# Adafruit_Servo_HAT_rev_A.net
KiCad netlist of a schematic drawn in EAGLE
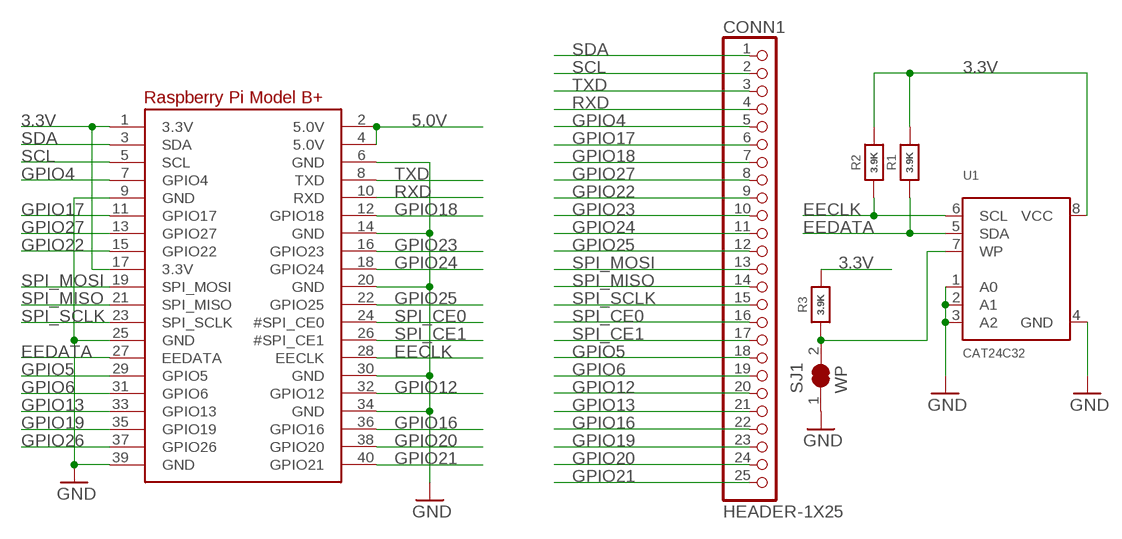
[diagram p0: schematic, sheet 1]
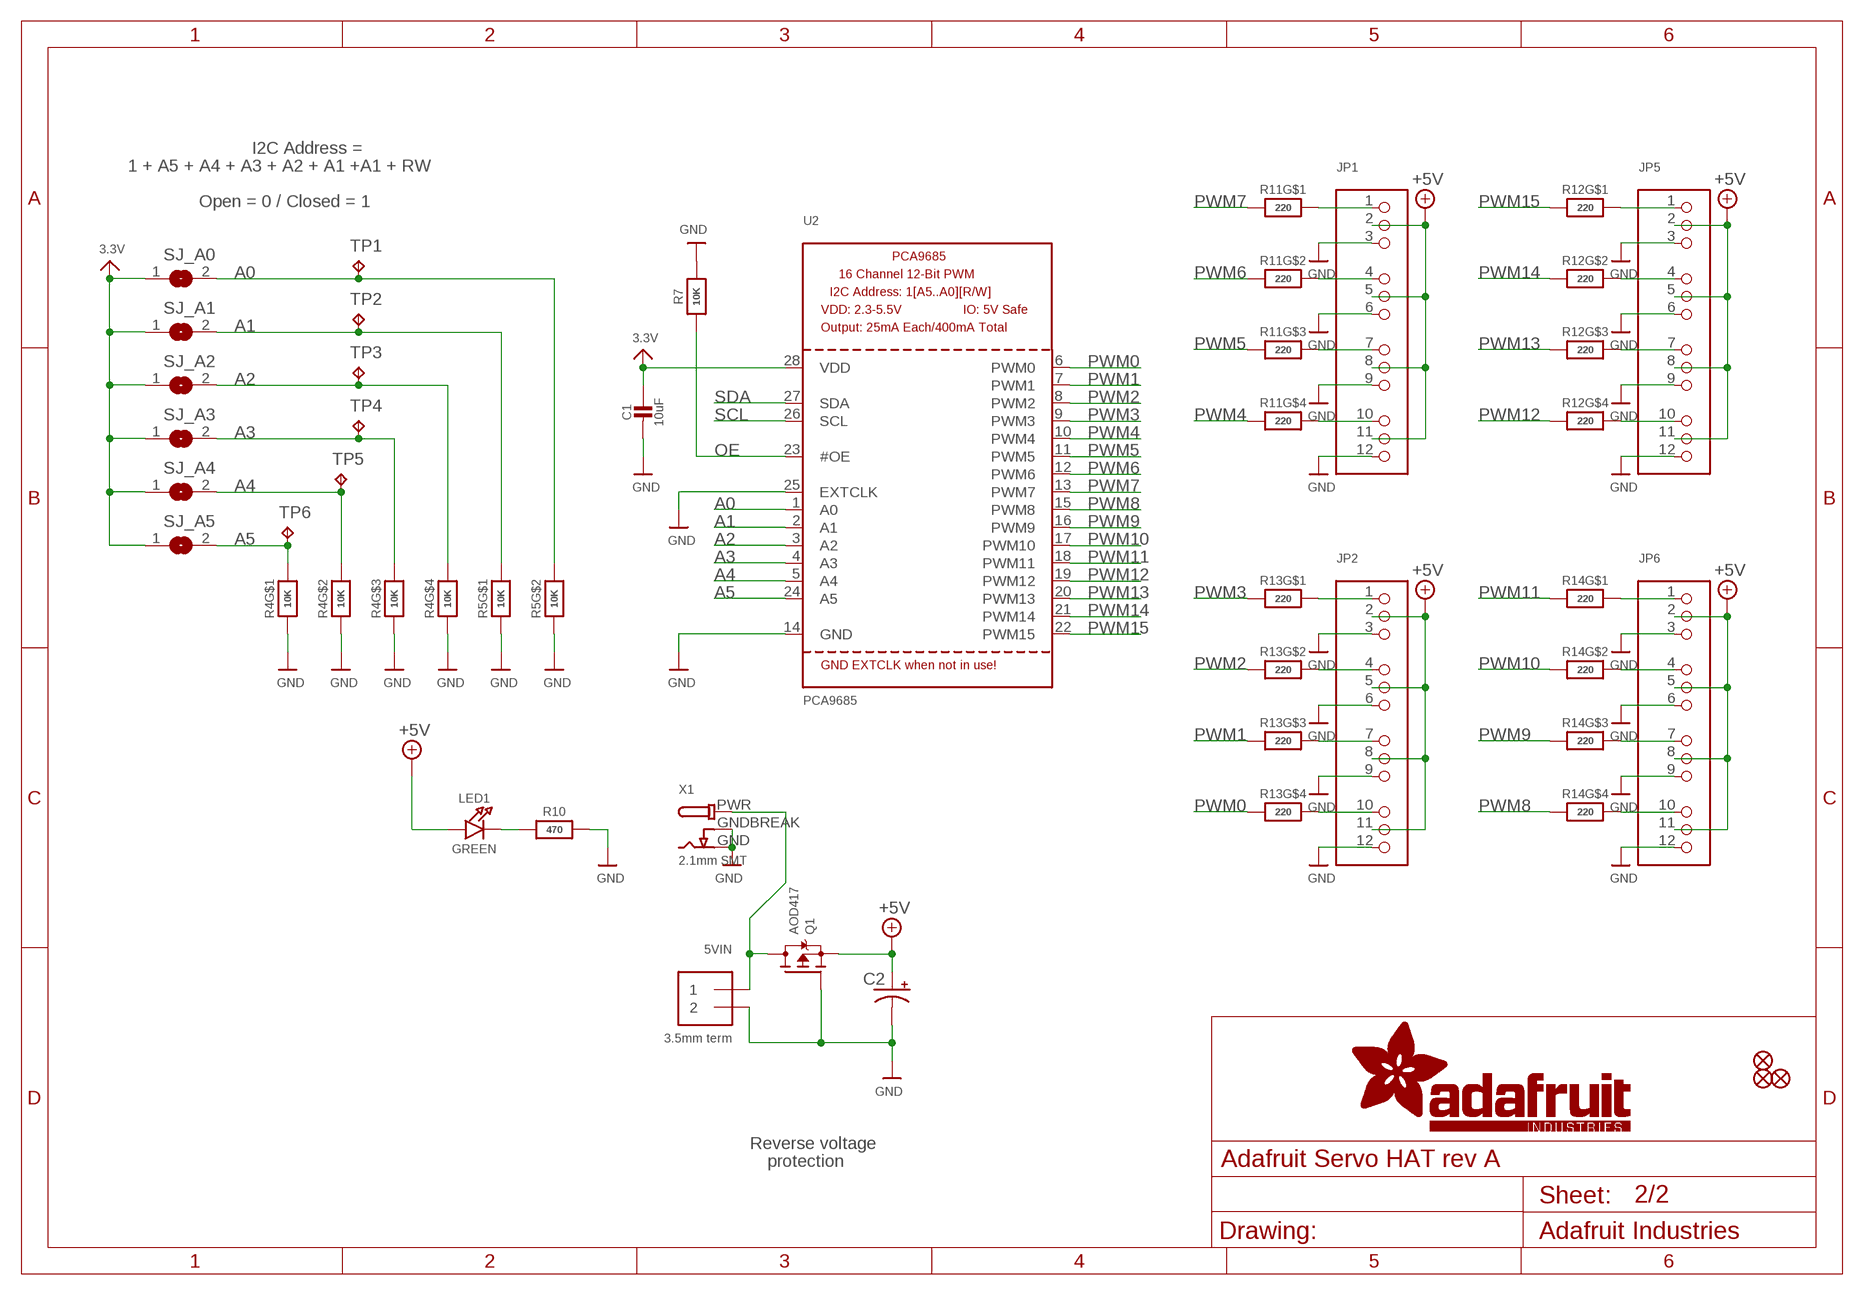
[diagram p1: schematic, sheet 2]

(export (version "E")
  (design (tool "Eeschema 10.0.6"))
  (components
    (comp (ref "5VIN")
      (value "3.5mm term")
      (footprint "eagle-import:TERMBLOCK_1X2-3.5MM")
      (libsource (lib "eagle-import") (part "TERMBLOCK_1X2"))
    )
    (comp (ref "C1")
      (value "10uF")
      (footprint "eagle-import:0805-NO")
      (libsource (lib "eagle-import") (part "CAP_CERAMIC0805-NOOUTLINE"))
    )
    (comp (ref "C2")
      (value "CPOL-USE3.5-8")
      (footprint "eagle-import:E3,5-8")
      (libsource (lib "eagle-import") (part "CPOL-USE3.5-8"))
    )
    (comp (ref "FID1")
      (value "FIDUCIAL\"\"")
      (footprint "eagle-import:FIDUCIAL_1MM")
      (libsource (lib "eagle-import") (part "FIDUCIAL{dblquote}{dblquote}"))
    )
    (comp (ref "FID2")
      (value "FIDUCIAL\"\"")
      (footprint "eagle-import:FIDUCIAL_1MM")
      (libsource (lib "eagle-import") (part "FIDUCIAL{dblquote}{dblquote}"))
    )
    (comp (ref "FID3")
      (value "FIDUCIAL\"\"")
      (footprint "eagle-import:FIDUCIAL_1MM")
      (fields (field (name "BOM") "EXCLUDE"))
      (libsource (lib "eagle-import") (part "FIDUCIAL{dblquote}{dblquote}"))
    )
    (comp (ref "JP1")
      (value "HEADER-3X04")
      (footprint "eagle-import:3X04")
      (libsource (lib "eagle-import") (part "HEADER-3X04"))
    )
    (comp (ref "JP2")
      (value "HEADER-3X04")
      (footprint "eagle-import:3X04")
      (libsource (lib "eagle-import") (part "HEADER-3X04"))
    )
    (comp (ref "JP5")
      (value "HEADER-3X04")
      (footprint "eagle-import:3X04")
      (libsource (lib "eagle-import") (part "HEADER-3X04"))
    )
    (comp (ref "JP6")
      (value "HEADER-3X04")
      (footprint "eagle-import:3X04")
      (libsource (lib "eagle-import") (part "HEADER-3X04"))
    )
    (comp (ref "LED1")
      (value "GREEN")
      (footprint "eagle-import:CHIPLED_0805_NOOUTLINE")
      (libsource (lib "eagle-import") (part "LED0805_NOOUTLINE"))
    )
    (comp (ref "Q1")
      (value "AOD417")
      (footprint "eagle-import:TO252")
      (libsource (lib "eagle-import") (part "MOSFET-PTO252"))
    )
    (comp (ref "R4")
      (value "10K")
      (footprint "eagle-import:RESPACK_4X0603")
      (libsource (lib "eagle-import") (part "RESISTOR_4PACK"))
    )
    (comp (ref "R5")
      (value "10K")
      (footprint "eagle-import:RESPACK_4X0603")
      (libsource (lib "eagle-import") (part "RESISTOR_4PACK"))
    )
    (comp (ref "R7")
      (value "10K")
      (footprint "eagle-import:0805-NO")
      (libsource (lib "eagle-import") (part "RESISTOR0805_NOOUTLINE"))
    )
    (comp (ref "R10")
      (value "470")
      (footprint "eagle-import:_0805MP")
      (libsource (lib "eagle-import") (part "RESISTOR_0805MP"))
    )
    (comp (ref "R11")
      (value "220")
      (footprint "eagle-import:RESPACK_4X0603")
      (libsource (lib "eagle-import") (part "RESISTOR_4PACK"))
    )
    (comp (ref "R12")
      (value "220")
      (footprint "eagle-import:RESPACK_4X0603")
      (libsource (lib "eagle-import") (part "RESISTOR_4PACK"))
    )
    (comp (ref "R13")
      (value "220")
      (footprint "eagle-import:RESPACK_4X0603")
      (libsource (lib "eagle-import") (part "RESISTOR_4PACK"))
    )
    (comp (ref "R14")
      (value "220")
      (footprint "eagle-import:RESPACK_4X0603")
      (libsource (lib "eagle-import") (part "RESISTOR_4PACK"))
    )
    (comp (ref "SJ_A0")
      (value "SOLDERJUMPERREFLOW_NOPASTE")
      (footprint "eagle-import:SOLDERJUMPER_REFLOW_NOPASTE")
      (libsource (lib "eagle-import") (part "SOLDERJUMPERREFLOW_NOPASTE"))
    )
    (comp (ref "SJ_A1")
      (value "SOLDERJUMPERREFLOW_NOPASTE")
      (footprint "eagle-import:SOLDERJUMPER_REFLOW_NOPASTE")
      (libsource (lib "eagle-import") (part "SOLDERJUMPERREFLOW_NOPASTE"))
    )
    (comp (ref "SJ_A2")
      (value "SOLDERJUMPERREFLOW_NOPASTE")
      (footprint "eagle-import:SOLDERJUMPER_REFLOW_NOPASTE")
      (libsource (lib "eagle-import") (part "SOLDERJUMPERREFLOW_NOPASTE"))
    )
    (comp (ref "SJ_A3")
      (value "SOLDERJUMPERREFLOW_NOPASTE")
      (footprint "eagle-import:SOLDERJUMPER_REFLOW_NOPASTE")
      (libsource (lib "eagle-import") (part "SOLDERJUMPERREFLOW_NOPASTE"))
    )
    (comp (ref "SJ_A4")
      (value "SOLDERJUMPERREFLOW_NOPASTE")
      (footprint "eagle-import:SOLDERJUMPER_REFLOW_NOPASTE")
      (libsource (lib "eagle-import") (part "SOLDERJUMPERREFLOW_NOPASTE"))
    )
    (comp (ref "SJ_A5")
      (value "SOLDERJUMPERREFLOW_NOPASTE")
      (footprint "eagle-import:SOLDERJUMPER_REFLOW_NOPASTE")
      (libsource (lib "eagle-import") (part "SOLDERJUMPERREFLOW_NOPASTE"))
    )
    (comp (ref "TP1")
      (value "TPB1,27")
      (footprint "eagle-import:B1,27")
      (libsource (lib "eagle-import") (part "TPB1,27"))
    )
    (comp (ref "TP2")
      (value "TPB1,27")
      (footprint "eagle-import:B1,27")
      (libsource (lib "eagle-import") (part "TPB1,27"))
    )
    (comp (ref "TP3")
      (value "TPB1,27")
      (footprint "eagle-import:B1,27")
      (libsource (lib "eagle-import") (part "TPB1,27"))
    )
    (comp (ref "TP4")
      (value "TPB1,27")
      (footprint "eagle-import:B1,27")
      (libsource (lib "eagle-import") (part "TPB1,27"))
    )
    (comp (ref "TP5")
      (value "TPB1,27")
      (footprint "eagle-import:B1,27")
      (libsource (lib "eagle-import") (part "TPB1,27"))
    )
    (comp (ref "TP6")
      (value "TPB1,27")
      (footprint "eagle-import:B1,27")
      (libsource (lib "eagle-import") (part "TPB1,27"))
    )
    (comp (ref "U2")
      (value "PCA9685")
      (footprint "eagle-import:TSSOP28")
      (libsource (lib "eagle-import") (part "PCA9685"))
    )
    (comp (ref "X1")
      (value "2.1mm SMT")
      (footprint "eagle-import:DCJACK_2MM_SMT")
      (libsource (lib "eagle-import") (part "DCBARRELSMT_CORRECT"))
    )
    (comp (ref "CONN1")
      (value "HEADER-1X25")
      (footprint "eagle-import:1X25_ROUND_70MIL")
      (libsource (lib "eagle-import") (part "HEADER-1X25"))
    )
    (comp (ref "R1")
      (value "3.9K")
      (footprint "eagle-import:0805-NO")
      (libsource (lib "eagle-import") (part "RESISTOR0805_NOOUTLINE"))
    )
    (comp (ref "R2")
      (value "3.9K")
      (footprint "eagle-import:0805-NO")
      (libsource (lib "eagle-import") (part "RESISTOR0805_NOOUTLINE"))
    )
    (comp (ref "R3")
      (value "3.9K")
      (footprint "eagle-import:0805-NO")
      (libsource (lib "eagle-import") (part "RESISTOR0805_NOOUTLINE"))
    )
    (comp (ref "RPI1")
      (value "RASPBERRYPI_BPLUS_HATSLOTS")
      (footprint "eagle-import:PI_HAT_SLOTS")
      (libsource (lib "eagle-import") (part "RASPBERRYPI_BPLUS_HATSLOTS"))
    )
    (comp (ref "SJ1")
      (value "WP")
      (footprint "eagle-import:SOLDERJUMPER_CLOSEDWIRE")
      (libsource (lib "eagle-import") (part "SOLDERJUMPER_CLOSED"))
    )
    (comp (ref "U1")
      (value "CAT24C32")
      (footprint "eagle-import:SOIC8_150MIL")
      (libsource (lib "eagle-import") (part "EEPROM_I2C_SOIC8_GENERIC"))
    )
  )
  (nets
    (net (code "1") (name "+5V") (class "Default")
      (node (ref "C2") (pin "+") (pinfunction "+_+") (pintype "passive"))
      (node (ref "JP1") (pin "11") (pinfunction "11_11") (pintype "passive"))
      (node (ref "JP1") (pin "2") (pinfunction "2_2") (pintype "passive"))
      (node (ref "JP1") (pin "5") (pinfunction "5_5") (pintype "passive"))
      (node (ref "JP1") (pin "8") (pinfunction "8_8") (pintype "passive"))
      (node (ref "JP2") (pin "11") (pinfunction "11_11") (pintype "passive"))
      (node (ref "JP2") (pin "2") (pinfunction "2_2") (pintype "passive"))
      (node (ref "JP2") (pin "5") (pinfunction "5_5") (pintype "passive"))
      (node (ref "JP2") (pin "8") (pinfunction "8_8") (pintype "passive"))
      (node (ref "JP5") (pin "11") (pinfunction "11_11") (pintype "passive"))
      (node (ref "JP5") (pin "2") (pinfunction "2_2") (pintype "passive"))
      (node (ref "JP5") (pin "5") (pinfunction "5_5") (pintype "passive"))
      (node (ref "JP5") (pin "8") (pinfunction "8_8") (pintype "passive"))
      (node (ref "JP6") (pin "11") (pinfunction "11_11") (pintype "passive"))
      (node (ref "JP6") (pin "2") (pinfunction "2_2") (pintype "passive"))
      (node (ref "JP6") (pin "5") (pinfunction "5_5") (pintype "passive"))
      (node (ref "JP6") (pin "8") (pinfunction "8_8") (pintype "passive"))
      (node (ref "LED1") (pin "A") (pinfunction "A_A") (pintype "passive"))
      (node (ref "Q1") (pin "2") (pinfunction "S_2") (pintype "passive"))
    )
    (net (code "2") (name "3.3V") (class "Default")
      (node (ref "C1") (pin "1") (pinfunction "1_1") (pintype "passive"))
      (node (ref "R1") (pin "2") (pinfunction "2_2") (pintype "passive"))
      (node (ref "R2") (pin "2") (pinfunction "2_2") (pintype "passive"))
      (node (ref "R3") (pin "2") (pinfunction "2_2") (pintype "passive"))
      (node (ref "RPI1") (pin "1") (pinfunction "3.3V_1") (pintype "power_in"))
      (node (ref "RPI1") (pin "17") (pinfunction "3.3V_17") (pintype "power_in"))
      (node (ref "SJ_A0") (pin "1") (pinfunction "1_1") (pintype "passive"))
      (node (ref "SJ_A1") (pin "1") (pinfunction "1_1") (pintype "passive"))
      (node (ref "SJ_A2") (pin "1") (pinfunction "1_1") (pintype "passive"))
      (node (ref "SJ_A3") (pin "1") (pinfunction "1_1") (pintype "passive"))
      (node (ref "SJ_A4") (pin "1") (pinfunction "1_1") (pintype "passive"))
      (node (ref "SJ_A5") (pin "1") (pinfunction "1_1") (pintype "passive"))
      (node (ref "U1") (pin "8") (pinfunction "VCC_8") (pintype "power_in"))
      (node (ref "U2") (pin "28") (pinfunction "VDD_28") (pintype "power_in"))
    )
    (net (code "3") (name "5.0V") (class "Default")
      (node (ref "RPI1") (pin "2") (pinfunction "5.0V_2") (pintype "power_in"))
      (node (ref "RPI1") (pin "4") (pinfunction "5.0V_4") (pintype "power_in"))
    )
    (net (code "4") (name "A0") (class "Default")
      (node (ref "R5") (pin "7") (pinfunction "2_7") (pintype "passive"))
      (node (ref "SJ_A0") (pin "2") (pinfunction "2_2") (pintype "passive"))
      (node (ref "TP1") (pin "TP") (pinfunction "TP_TP") (pintype "input"))
      (node (ref "U2") (pin "1") (pinfunction "A0_1") (pintype "bidirectional"))
    )
    (net (code "5") (name "A1") (class "Default")
      (node (ref "R5") (pin "8") (pinfunction "2_8") (pintype "passive"))
      (node (ref "SJ_A1") (pin "2") (pinfunction "2_2") (pintype "passive"))
      (node (ref "TP2") (pin "TP") (pinfunction "TP_TP") (pintype "input"))
      (node (ref "U2") (pin "2") (pinfunction "A1_2") (pintype "bidirectional"))
    )
    (net (code "6") (name "A2") (class "Default")
      (node (ref "R4") (pin "5") (pinfunction "2_5") (pintype "passive"))
      (node (ref "SJ_A2") (pin "2") (pinfunction "2_2") (pintype "passive"))
      (node (ref "TP3") (pin "TP") (pinfunction "TP_TP") (pintype "input"))
      (node (ref "U2") (pin "3") (pinfunction "A2_3") (pintype "bidirectional"))
    )
    (net (code "7") (name "A3") (class "Default")
      (node (ref "R4") (pin "6") (pinfunction "2_6") (pintype "passive"))
      (node (ref "SJ_A3") (pin "2") (pinfunction "2_2") (pintype "passive"))
      (node (ref "TP4") (pin "TP") (pinfunction "TP_TP") (pintype "input"))
      (node (ref "U2") (pin "4") (pinfunction "A3_4") (pintype "bidirectional"))
    )
    (net (code "8") (name "A4") (class "Default")
      (node (ref "R4") (pin "7") (pinfunction "2_7") (pintype "passive"))
      (node (ref "SJ_A4") (pin "2") (pinfunction "2_2") (pintype "passive"))
      (node (ref "TP5") (pin "TP") (pinfunction "TP_TP") (pintype "input"))
      (node (ref "U2") (pin "5") (pinfunction "A4_5") (pintype "bidirectional"))
    )
    (net (code "9") (name "A5") (class "Default")
      (node (ref "R4") (pin "8") (pinfunction "2_8") (pintype "passive"))
      (node (ref "SJ_A5") (pin "2") (pinfunction "2_2") (pintype "passive"))
      (node (ref "TP6") (pin "TP") (pinfunction "TP_TP") (pintype "input"))
      (node (ref "U2") (pin "24") (pinfunction "A5_24") (pintype "bidirectional"))
    )
    (net (code "10") (name "EECLK") (class "Default")
      (node (ref "R2") (pin "1") (pinfunction "1_1") (pintype "passive"))
      (node (ref "RPI1") (pin "28") (pinfunction "EECLK_28") (pintype "power_in"))
      (node (ref "U1") (pin "6") (pinfunction "SCL_6") (pintype "input"))
    )
    (net (code "11") (name "EEDATA") (class "Default")
      (node (ref "R1") (pin "1") (pinfunction "1_1") (pintype "passive"))
      (node (ref "RPI1") (pin "27") (pinfunction "EEDATA_27") (pintype "bidirectional"))
      (node (ref "U1") (pin "5") (pinfunction "SDA_5") (pintype "bidirectional"))
    )
    (net (code "12") (name "GND") (class "Default")
      (node (ref "5VIN") (pin "2") (pinfunction "2_2") (pintype "passive"))
      (node (ref "C1") (pin "2") (pinfunction "2_2") (pintype "passive"))
      (node (ref "C2") (pin "-") (pinfunction "-_-") (pintype "passive"))
      (node (ref "JP1") (pin "12") (pinfunction "12_12") (pintype "passive"))
      (node (ref "JP1") (pin "3") (pinfunction "3_3") (pintype "passive"))
      (node (ref "JP1") (pin "6") (pinfunction "6_6") (pintype "passive"))
      (node (ref "JP1") (pin "9") (pinfunction "9_9") (pintype "passive"))
      (node (ref "JP2") (pin "12") (pinfunction "12_12") (pintype "passive"))
      (node (ref "JP2") (pin "3") (pinfunction "3_3") (pintype "passive"))
      (node (ref "JP2") (pin "6") (pinfunction "6_6") (pintype "passive"))
      (node (ref "JP2") (pin "9") (pinfunction "9_9") (pintype "passive"))
      (node (ref "JP5") (pin "12") (pinfunction "12_12") (pintype "passive"))
      (node (ref "JP5") (pin "3") (pinfunction "3_3") (pintype "passive"))
      (node (ref "JP5") (pin "6") (pinfunction "6_6") (pintype "passive"))
      (node (ref "JP5") (pin "9") (pinfunction "9_9") (pintype "passive"))
      (node (ref "JP6") (pin "12") (pinfunction "12_12") (pintype "passive"))
      (node (ref "JP6") (pin "3") (pinfunction "3_3") (pintype "passive"))
      (node (ref "JP6") (pin "6") (pinfunction "6_6") (pintype "passive"))
      (node (ref "JP6") (pin "9") (pinfunction "9_9") (pintype "passive"))
      (node (ref "Q1") (pin "1") (pinfunction "G_1") (pintype "passive"))
      (node (ref "R10") (pin "2") (pinfunction "2_2") (pintype "passive"))
      (node (ref "R4") (pin "1") (pinfunction "1_1") (pintype "passive"))
      (node (ref "R4") (pin "2") (pinfunction "1_2") (pintype "passive"))
      (node (ref "R4") (pin "3") (pinfunction "1_3") (pintype "passive"))
      (node (ref "R4") (pin "4") (pinfunction "1_4") (pintype "passive"))
      (node (ref "R5") (pin "1") (pinfunction "1_1") (pintype "passive"))
      (node (ref "R5") (pin "2") (pinfunction "1_2") (pintype "passive"))
      (node (ref "R7") (pin "2") (pinfunction "2_2") (pintype "passive"))
      (node (ref "RPI1") (pin "14") (pinfunction "GND_14") (pintype "power_in"))
      (node (ref "RPI1") (pin "20") (pinfunction "GND_20") (pintype "power_in"))
      (node (ref "RPI1") (pin "25") (pinfunction "GND_25") (pintype "power_in"))
      (node (ref "RPI1") (pin "30") (pinfunction "GND_30") (pintype "bidirectional"))
      (node (ref "RPI1") (pin "34") (pinfunction "GND_34") (pintype "bidirectional"))
      (node (ref "RPI1") (pin "39") (pinfunction "GND_39") (pintype "power_in"))
      (node (ref "RPI1") (pin "6") (pinfunction "GND_6") (pintype "power_in"))
      (node (ref "RPI1") (pin "9") (pinfunction "GND_9") (pintype "power_in"))
      (node (ref "SJ1") (pin "1") (pinfunction "1_1") (pintype "passive"))
      (node (ref "U1") (pin "1") (pinfunction "A0_1") (pintype "input"))
      (node (ref "U1") (pin "2") (pinfunction "A1_2") (pintype "input"))
      (node (ref "U1") (pin "3") (pinfunction "A2_3") (pintype "input"))
      (node (ref "U1") (pin "4") (pinfunction "GND_4") (pintype "power_in"))
      (node (ref "U2") (pin "14") (pinfunction "GND_14") (pintype "power_in"))
      (node (ref "U2") (pin "25") (pinfunction "EXTCLK_25") (pintype "input"))
      (node (ref "X1") (pin "GND") (pinfunction "GND_GND") (pintype "power_in"))
      (node (ref "X1") (pin "GNDBREAK") (pinfunction "GNDBREAK_GNDBREAK") (pintype "power_in"))
    )
    (net (code "13") (name "GPIO4") (class "Default")
      (node (ref "CONN1") (pin "5") (pinfunction "5_5") (pintype "passive"))
      (node (ref "RPI1") (pin "7") (pinfunction "GPIO4_7") (pintype "bidirectional"))
    )
    (net (code "14") (name "GPIO5") (class "Default")
      (node (ref "CONN1") (pin "18") (pinfunction "18_18") (pintype "passive"))
      (node (ref "RPI1") (pin "29") (pinfunction "GPIO5_29") (pintype "bidirectional"))
    )
    (net (code "15") (name "GPIO6") (class "Default")
      (node (ref "CONN1") (pin "19") (pinfunction "19_19") (pintype "passive"))
      (node (ref "RPI1") (pin "31") (pinfunction "GPIO6_31") (pintype "power_in"))
    )
    (net (code "16") (name "GPIO12") (class "Default")
      (node (ref "CONN1") (pin "20") (pinfunction "20_20") (pintype "passive"))
      (node (ref "RPI1") (pin "32") (pinfunction "GPIO12_32") (pintype "bidirectional"))
    )
    (net (code "17") (name "GPIO13") (class "Default")
      (node (ref "CONN1") (pin "21") (pinfunction "21_21") (pintype "passive"))
      (node (ref "RPI1") (pin "33") (pinfunction "GPIO13_33") (pintype "bidirectional"))
    )
    (net (code "18") (name "GPIO16") (class "Default")
      (node (ref "CONN1") (pin "22") (pinfunction "22_22") (pintype "passive"))
      (node (ref "RPI1") (pin "36") (pinfunction "GPIO16_36") (pintype "power_in"))
    )
    (net (code "19") (name "GPIO17") (class "Default")
      (node (ref "CONN1") (pin "6") (pinfunction "6_6") (pintype "passive"))
      (node (ref "RPI1") (pin "11") (pinfunction "GPIO17_11") (pintype "bidirectional"))
    )
    (net (code "20") (name "GPIO18") (class "Default")
      (node (ref "CONN1") (pin "7") (pinfunction "7_7") (pintype "passive"))
      (node (ref "RPI1") (pin "12") (pinfunction "GPIO18_12") (pintype "bidirectional"))
    )
    (net (code "21") (name "GPIO19") (class "Default")
      (node (ref "CONN1") (pin "23") (pinfunction "23_23") (pintype "passive"))
      (node (ref "RPI1") (pin "35") (pinfunction "GPIO19_35") (pintype "bidirectional"))
    )
    (net (code "22") (name "GPIO20") (class "Default")
      (node (ref "CONN1") (pin "24") (pinfunction "24_24") (pintype "passive"))
      (node (ref "RPI1") (pin "38") (pinfunction "GPIO20_38") (pintype "bidirectional"))
    )
    (net (code "23") (name "GPIO21") (class "Default")
      (node (ref "CONN1") (pin "25") (pinfunction "25_25") (pintype "passive"))
      (node (ref "RPI1") (pin "40") (pinfunction "GPIO21_40") (pintype "bidirectional"))
    )
    (net (code "24") (name "GPIO22") (class "Default")
      (node (ref "CONN1") (pin "9") (pinfunction "9_9") (pintype "passive"))
      (node (ref "RPI1") (pin "15") (pinfunction "GPIO22_15") (pintype "bidirectional"))
    )
    (net (code "25") (name "GPIO23") (class "Default")
      (node (ref "CONN1") (pin "10") (pinfunction "10_10") (pintype "passive"))
      (node (ref "RPI1") (pin "16") (pinfunction "GPIO23_16") (pintype "bidirectional"))
    )
    (net (code "26") (name "GPIO24") (class "Default")
      (node (ref "CONN1") (pin "11") (pinfunction "11_11") (pintype "passive"))
      (node (ref "RPI1") (pin "18") (pinfunction "GPIO24_18") (pintype "bidirectional"))
    )
    (net (code "27") (name "GPIO25") (class "Default")
      (node (ref "CONN1") (pin "12") (pinfunction "12_12") (pintype "passive"))
      (node (ref "RPI1") (pin "22") (pinfunction "GPIO25_22") (pintype "bidirectional"))
    )
    (net (code "28") (name "GPIO26") (class "Default")
      (node (ref "RPI1") (pin "37") (pinfunction "GPIO26_37") (pintype "bidirectional"))
    )
    (net (code "29") (name "GPIO27") (class "Default")
      (node (ref "CONN1") (pin "8") (pinfunction "8_8") (pintype "passive"))
      (node (ref "RPI1") (pin "13") (pinfunction "GPIO27_13") (pintype "bidirectional"))
    )
    (net (code "30") (name "Net-(LED1-PadC)") (class "Default")
      (node (ref "LED1") (pin "C") (pinfunction "C_C") (pintype "passive"))
      (node (ref "R10") (pin "1") (pinfunction "1_1") (pintype "passive"))
    )
    (net (code "31") (name "Net-(Q1-D)") (class "Default")
      (node (ref "5VIN") (pin "1") (pinfunction "1_1") (pintype "passive"))
      (node (ref "Q1") (pin "3") (pinfunction "D_3") (pintype "passive"))
      (node (ref "X1") (pin "PWR") (pinfunction "PWR_PWR") (pintype "power_in"))
    )
    (net (code "32") (name "Net-(R11A-2)") (class "Default")
      (node (ref "JP1") (pin "1") (pinfunction "1_1") (pintype "passive"))
      (node (ref "R11") (pin "8") (pinfunction "2_8") (pintype "passive"))
    )
    (net (code "33") (name "Net-(R11B-2)") (class "Default")
      (node (ref "JP1") (pin "4") (pinfunction "4_4") (pintype "passive"))
      (node (ref "R11") (pin "7") (pinfunction "2_7") (pintype "passive"))
    )
    (net (code "34") (name "Net-(R11C-2)") (class "Default")
      (node (ref "JP1") (pin "7") (pinfunction "7_7") (pintype "passive"))
      (node (ref "R11") (pin "6") (pinfunction "2_6") (pintype "passive"))
    )
    (net (code "35") (name "Net-(R11D-2)") (class "Default")
      (node (ref "JP1") (pin "10") (pinfunction "10_10") (pintype "passive"))
      (node (ref "R11") (pin "5") (pinfunction "2_5") (pintype "passive"))
    )
    (net (code "36") (name "Net-(R12A-2)") (class "Default")
      (node (ref "JP5") (pin "1") (pinfunction "1_1") (pintype "passive"))
      (node (ref "R12") (pin "8") (pinfunction "2_8") (pintype "passive"))
    )
    (net (code "37") (name "Net-(R12B-2)") (class "Default")
      (node (ref "JP5") (pin "4") (pinfunction "4_4") (pintype "passive"))
      (node (ref "R12") (pin "7") (pinfunction "2_7") (pintype "passive"))
    )
    (net (code "38") (name "Net-(R12C-2)") (class "Default")
      (node (ref "JP5") (pin "7") (pinfunction "7_7") (pintype "passive"))
      (node (ref "R12") (pin "6") (pinfunction "2_6") (pintype "passive"))
    )
    (net (code "39") (name "Net-(R12D-2)") (class "Default")
      (node (ref "JP5") (pin "10") (pinfunction "10_10") (pintype "passive"))
      (node (ref "R12") (pin "5") (pinfunction "2_5") (pintype "passive"))
    )
    (net (code "40") (name "Net-(R13A-2)") (class "Default")
      (node (ref "JP2") (pin "1") (pinfunction "1_1") (pintype "passive"))
      (node (ref "R13") (pin "8") (pinfunction "2_8") (pintype "passive"))
    )
    (net (code "41") (name "Net-(R13B-2)") (class "Default")
      (node (ref "JP2") (pin "4") (pinfunction "4_4") (pintype "passive"))
      (node (ref "R13") (pin "7") (pinfunction "2_7") (pintype "passive"))
    )
    (net (code "42") (name "Net-(R13C-2)") (class "Default")
      (node (ref "JP2") (pin "7") (pinfunction "7_7") (pintype "passive"))
      (node (ref "R13") (pin "6") (pinfunction "2_6") (pintype "passive"))
    )
    (net (code "43") (name "Net-(R13D-2)") (class "Default")
      (node (ref "JP2") (pin "10") (pinfunction "10_10") (pintype "passive"))
      (node (ref "R13") (pin "5") (pinfunction "2_5") (pintype "passive"))
    )
    (net (code "44") (name "Net-(R14A-2)") (class "Default")
      (node (ref "JP6") (pin "1") (pinfunction "1_1") (pintype "passive"))
      (node (ref "R14") (pin "8") (pinfunction "2_8") (pintype "passive"))
    )
    (net (code "45") (name "Net-(R14B-2)") (class "Default")
      (node (ref "JP6") (pin "4") (pinfunction "4_4") (pintype "passive"))
      (node (ref "R14") (pin "7") (pinfunction "2_7") (pintype "passive"))
    )
    (net (code "46") (name "Net-(R14C-2)") (class "Default")
      (node (ref "JP6") (pin "7") (pinfunction "7_7") (pintype "passive"))
      (node (ref "R14") (pin "6") (pinfunction "2_6") (pintype "passive"))
    )
    (net (code "47") (name "Net-(R14D-2)") (class "Default")
      (node (ref "JP6") (pin "10") (pinfunction "10_10") (pintype "passive"))
      (node (ref "R14") (pin "5") (pinfunction "2_5") (pintype "passive"))
    )
    (net (code "48") (name "Net-(U1-WP)") (class "Default")
      (node (ref "R3") (pin "1") (pinfunction "1_1") (pintype "passive"))
      (node (ref "SJ1") (pin "2") (pinfunction "2_2") (pintype "passive"))
      (node (ref "U1") (pin "7") (pinfunction "WP_7") (pintype "input"))
    )
    (net (code "49") (name "OE") (class "Default")
      (node (ref "R7") (pin "1") (pinfunction "1_1") (pintype "passive"))
      (node (ref "U2") (pin "23") (pinfunction "#OE_23") (pintype "input"))
    )
    (net (code "50") (name "PWM0") (class "Default")
      (node (ref "R13") (pin "4") (pinfunction "1_4") (pintype "passive"))
      (node (ref "U2") (pin "6") (pinfunction "PWM0_6") (pintype "output"))
    )
    (net (code "51") (name "PWM1") (class "Default")
      (node (ref "R13") (pin "3") (pinfunction "1_3") (pintype "passive"))
      (node (ref "U2") (pin "7") (pinfunction "PWM1_7") (pintype "output"))
    )
    (net (code "52") (name "PWM2") (class "Default")
      (node (ref "R13") (pin "2") (pinfunction "1_2") (pintype "passive"))
      (node (ref "U2") (pin "8") (pinfunction "PWM2_8") (pintype "output"))
    )
    (net (code "53") (name "PWM3") (class "Default")
      (node (ref "R13") (pin "1") (pinfunction "1_1") (pintype "passive"))
      (node (ref "U2") (pin "9") (pinfunction "PWM3_9") (pintype "output"))
    )
    (net (code "54") (name "PWM4") (class "Default")
      (node (ref "R11") (pin "4") (pinfunction "1_4") (pintype "passive"))
      (node (ref "U2") (pin "10") (pinfunction "PWM4_10") (pintype "output"))
    )
    (net (code "55") (name "PWM5") (class "Default")
      (node (ref "R11") (pin "3") (pinfunction "1_3") (pintype "passive"))
      (node (ref "U2") (pin "11") (pinfunction "PWM5_11") (pintype "output"))
    )
    (net (code "56") (name "PWM6") (class "Default")
      (node (ref "R11") (pin "2") (pinfunction "1_2") (pintype "passive"))
      (node (ref "U2") (pin "12") (pinfunction "PWM6_12") (pintype "output"))
    )
    (net (code "57") (name "PWM7") (class "Default")
      (node (ref "R11") (pin "1") (pinfunction "1_1") (pintype "passive"))
      (node (ref "U2") (pin "13") (pinfunction "PWM7_13") (pintype "output"))
    )
    (net (code "58") (name "PWM8") (class "Default")
      (node (ref "R14") (pin "4") (pinfunction "1_4") (pintype "passive"))
      (node (ref "U2") (pin "15") (pinfunction "PWM8_15") (pintype "output"))
    )
    (net (code "59") (name "PWM9") (class "Default")
      (node (ref "R14") (pin "3") (pinfunction "1_3") (pintype "passive"))
      (node (ref "U2") (pin "16") (pinfunction "PWM9_16") (pintype "output"))
    )
    (net (code "60") (name "PWM10") (class "Default")
      (node (ref "R14") (pin "2") (pinfunction "1_2") (pintype "passive"))
      (node (ref "U2") (pin "17") (pinfunction "PWM10_17") (pintype "output"))
    )
    (net (code "61") (name "PWM11") (class "Default")
      (node (ref "R14") (pin "1") (pinfunction "1_1") (pintype "passive"))
      (node (ref "U2") (pin "18") (pinfunction "PWM11_18") (pintype "output"))
    )
    (net (code "62") (name "PWM12") (class "Default")
      (node (ref "R12") (pin "4") (pinfunction "1_4") (pintype "passive"))
      (node (ref "U2") (pin "19") (pinfunction "PWM12_19") (pintype "output"))
    )
    (net (code "63") (name "PWM13") (class "Default")
      (node (ref "R12") (pin "3") (pinfunction "1_3") (pintype "passive"))
      (node (ref "U2") (pin "20") (pinfunction "PWM13_20") (pintype "output"))
    )
    (net (code "64") (name "PWM14") (class "Default")
      (node (ref "R12") (pin "2") (pinfunction "1_2") (pintype "passive"))
      (node (ref "U2") (pin "21") (pinfunction "PWM14_21") (pintype "output"))
    )
    (net (code "65") (name "PWM15") (class "Default")
      (node (ref "R12") (pin "1") (pinfunction "1_1") (pintype "passive"))
      (node (ref "U2") (pin "22") (pinfunction "PWM15_22") (pintype "output"))
    )
    (net (code "66") (name "RXD") (class "Default")
      (node (ref "CONN1") (pin "4") (pinfunction "4_4") (pintype "passive"))
      (node (ref "RPI1") (pin "10") (pinfunction "RXD_10") (pintype "bidirectional"))
    )
    (net (code "67") (name "SCL") (class "Default")
      (node (ref "CONN1") (pin "2") (pinfunction "2_2") (pintype "passive"))
      (node (ref "RPI1") (pin "5") (pinfunction "SCL_5") (pintype "bidirectional"))
      (node (ref "U2") (pin "26") (pinfunction "SCL_26") (pintype "bidirectional"))
    )
    (net (code "68") (name "SDA") (class "Default")
      (node (ref "CONN1") (pin "1") (pinfunction "1_1") (pintype "passive"))
      (node (ref "RPI1") (pin "3") (pinfunction "SDA_3") (pintype "bidirectional"))
      (node (ref "U2") (pin "27") (pinfunction "SDA_27") (pintype "bidirectional"))
    )
    (net (code "69") (name "SPI_CE0") (class "Default")
      (node (ref "CONN1") (pin "16") (pinfunction "16_16") (pintype "passive"))
      (node (ref "RPI1") (pin "24") (pinfunction "#SPI_CE0_24") (pintype "bidirectional"))
    )
    (net (code "70") (name "SPI_CE1") (class "Default")
      (node (ref "CONN1") (pin "17") (pinfunction "17_17") (pintype "passive"))
      (node (ref "RPI1") (pin "26") (pinfunction "#SPI_CE1_26") (pintype "bidirectional"))
    )
    (net (code "71") (name "SPI_MISO") (class "Default")
      (node (ref "CONN1") (pin "14") (pinfunction "14_14") (pintype "passive"))
      (node (ref "RPI1") (pin "21") (pinfunction "SPI_MISO_21") (pintype "bidirectional"))
    )
    (net (code "72") (name "SPI_MOSI") (class "Default")
      (node (ref "CONN1") (pin "13") (pinfunction "13_13") (pintype "passive"))
      (node (ref "RPI1") (pin "19") (pinfunction "SPI_MOSI_19") (pintype "bidirectional"))
    )
    (net (code "73") (name "SPI_SCLK") (class "Default")
      (node (ref "CONN1") (pin "15") (pinfunction "15_15") (pintype "passive"))
      (node (ref "RPI1") (pin "23") (pinfunction "SPI_SCLK_23") (pintype "bidirectional"))
    )
    (net (code "74") (name "TXD") (class "Default")
      (node (ref "CONN1") (pin "3") (pinfunction "3_3") (pintype "passive"))
      (node (ref "RPI1") (pin "8") (pinfunction "TXD_8") (pintype "output"))
    )
  )
)
